# TSOC_ESP32S.net
KiCad netlist of a schematic drawn in EAGLE
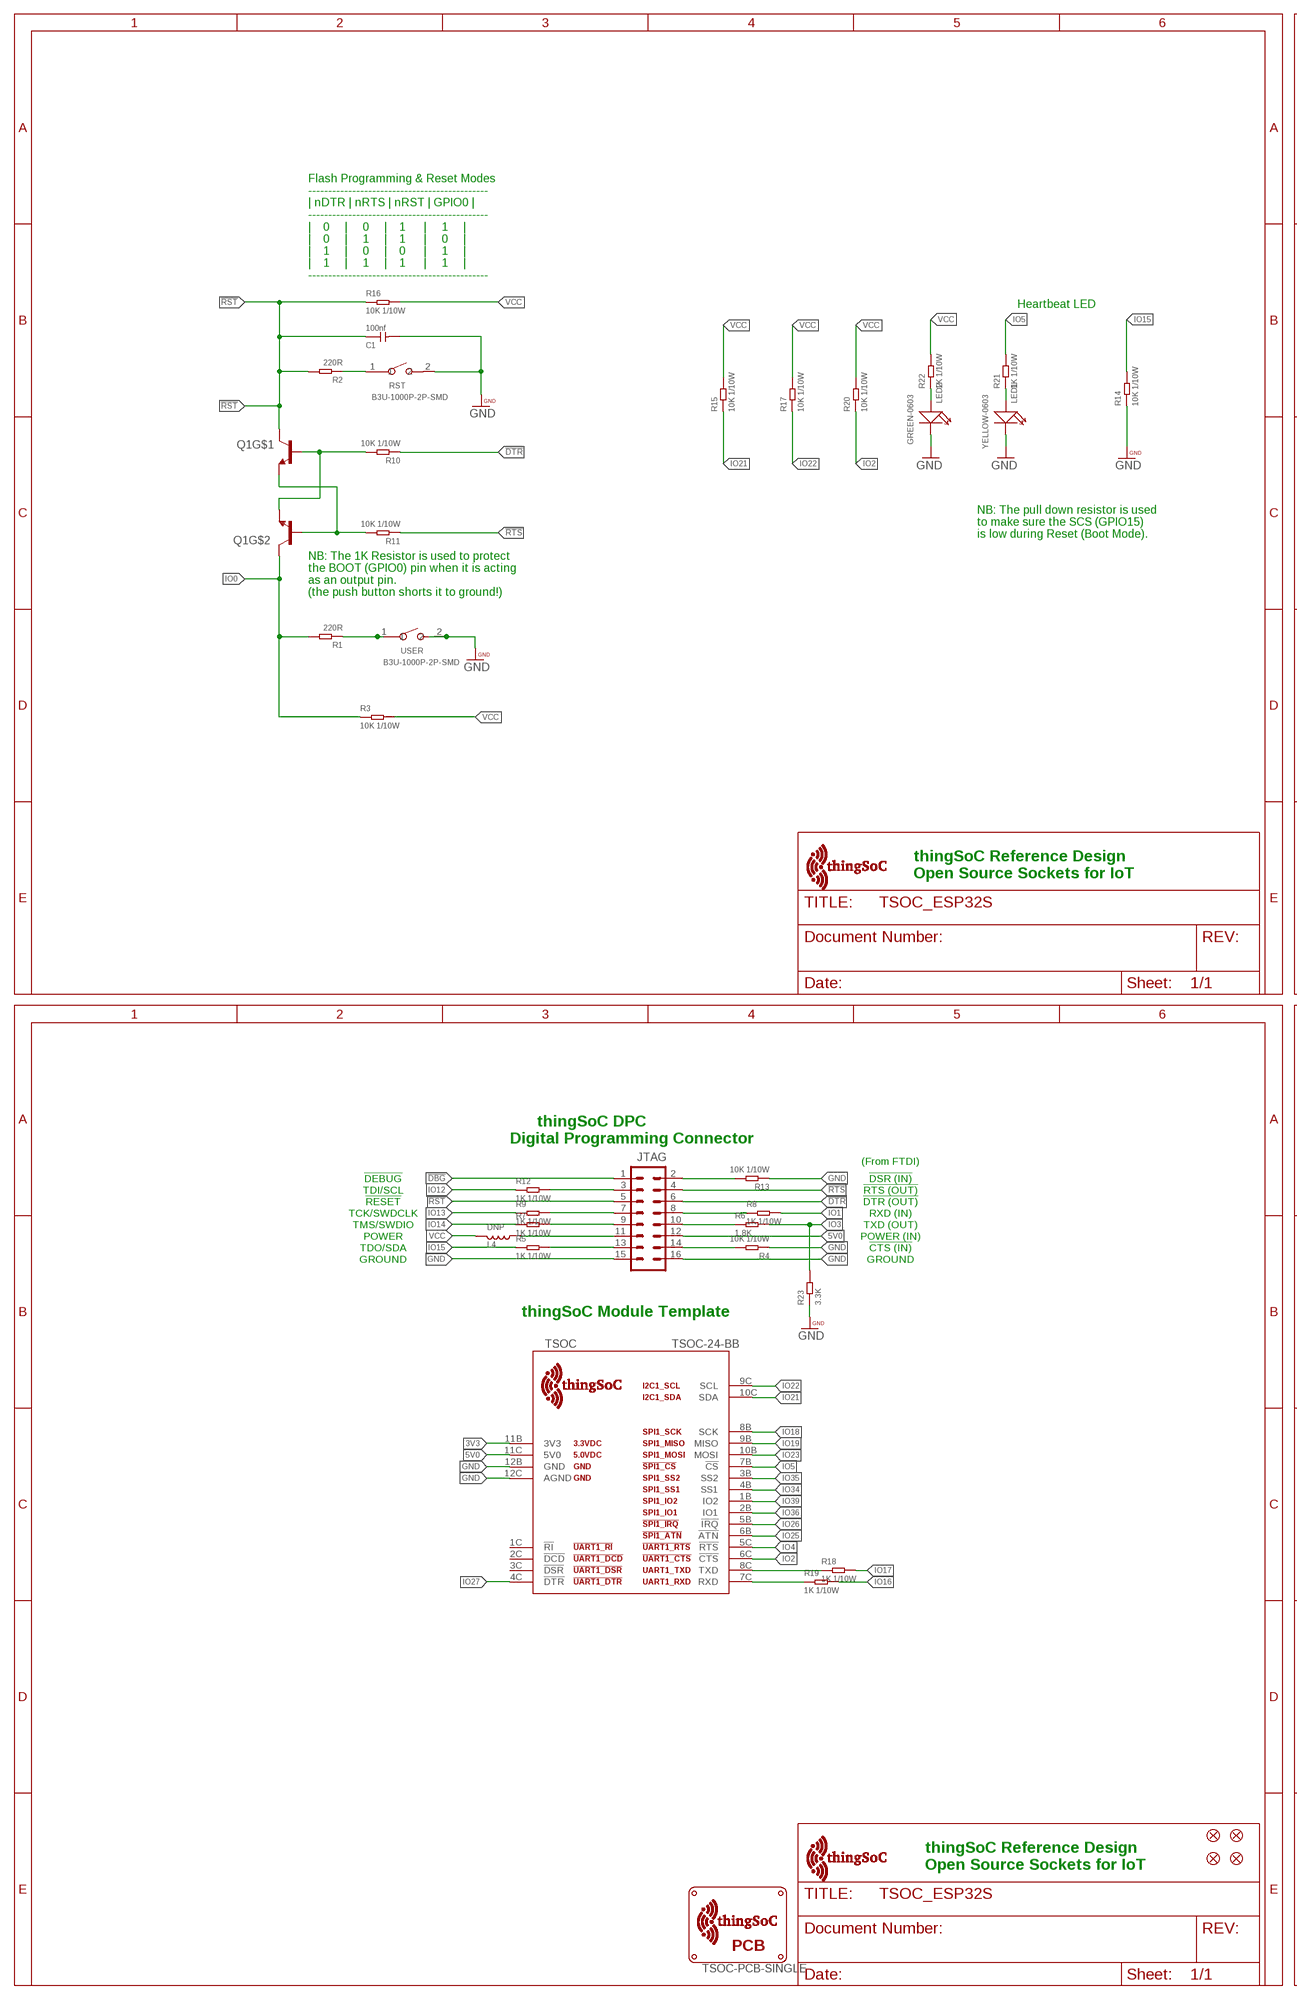
[diagram p0: schematic, sheet 1, part 1 of 2]
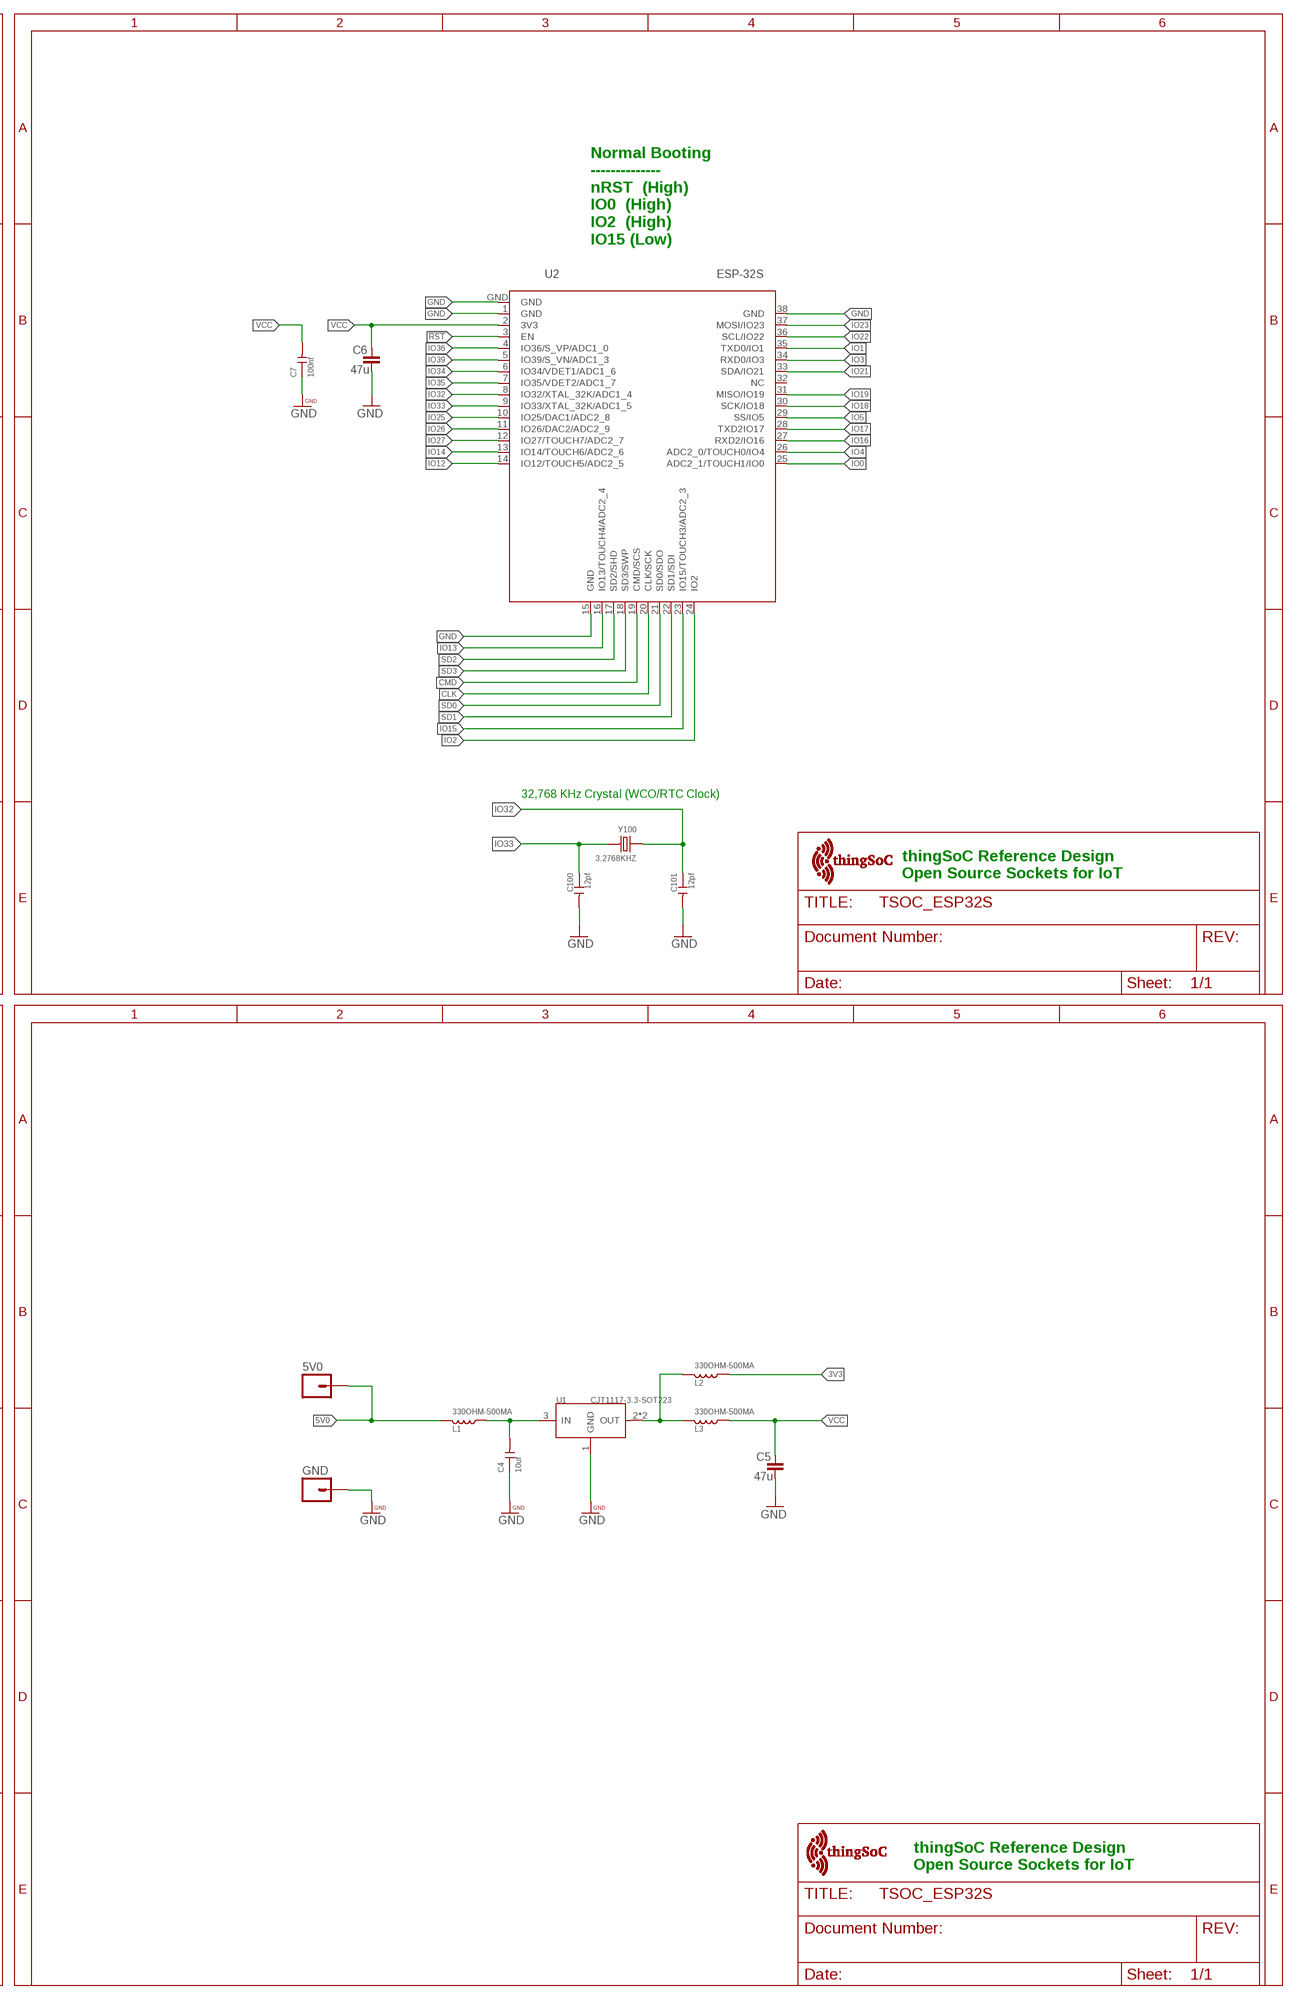
[diagram p1: schematic, sheet 1, part 2 of 2]

(export (version "E")
  (design (tool "Eeschema 10.0.6"))
  (components
    (comp (ref "$$U$1")
      (value "TSOC-LOGO-SMALL")
      (footprint "eagle-import:TSOC-LOGO-SML")
      (libsource (lib "eagle-import") (part "TSOC-LOGO-SMALL"))
    )
    (comp (ref "$$U$2")
      (value "TSOC-LOGO-SMALL")
      (footprint "eagle-import:TSOC-LOGO-SML")
      (libsource (lib "eagle-import") (part "TSOC-LOGO-SMALL"))
    )
    (comp (ref "5V0")
      (value "M01PTH")
      (footprint "eagle-import:1X01")
      (libsource (lib "eagle-import") (part "M01PTH"))
    )
    (comp (ref "BRD")
      (value "TSOC-PCB-SINGLE")
      (footprint "eagle-import:TSOC-BB-BRD-DIM")
      (libsource (lib "eagle-import") (part "TSOC-PCB-SINGLE"))
    )
    (comp (ref "C1")
      (value "100nf")
      (footprint "eagle-import:C0603")
      (fields (field (name "MPN") "CC0603KRX7R9BB104"))
      (libsource (lib "eagle-import") (part "CERAMIC-100NF-50V-10%-X7R(0603)"))
    )
    (comp (ref "C4")
      (value "10uf")
      (footprint "eagle-import:C0603")
      (fields (field (name "MPN") "CC0603KRX5R6BB106"))
      (libsource (lib "eagle-import") (part "CERAMIC-10UF-10V-10%-X5R(0603)"))
    )
    (comp (ref "C5")
      (value "47u")
      (footprint "eagle-import:C1206")
      (libsource (lib "eagle-import") (part "CAPACITOR-1206"))
    )
    (comp (ref "C6")
      (value "47u")
      (footprint "eagle-import:C1206")
      (libsource (lib "eagle-import") (part "CAPACITOR-1206"))
    )
    (comp (ref "C7")
      (value "100nf")
      (footprint "eagle-import:C0603")
      (fields (field (name "MPN") "CC0603KRX5R6BB106"))
      (libsource (lib "eagle-import") (part "CERAMIC-10UF-10V-10%-X5R(0603)"))
    )
    (comp (ref "C100")
      (value "12pf")
      (footprint "eagle-import:C0603")
      (fields (field (name "MPN") "CC0603JRNPO9BN120"))
      (libsource (lib "eagle-import") (part "CERAMIC-12PF-50V-5%-NPO(0603)"))
    )
    (comp (ref "C101")
      (value "12pf")
      (footprint "eagle-import:C0603")
      (fields (field (name "MPN") "CC0603JRNPO9BN120"))
      (libsource (lib "eagle-import") (part "CERAMIC-12PF-50V-5%-NPO(0603)"))
    )
    (comp (ref "FID1")
      (value "FIDUCIALUFIDUCIAL")
      (footprint "eagle-import:MICRO-FIDUCIAL")
      (libsource (lib "eagle-import") (part "FIDUCIALUFIDUCIAL"))
    )
    (comp (ref "FID2")
      (value "FIDUCIALUFIDUCIAL")
      (footprint "eagle-import:MICRO-FIDUCIAL")
      (libsource (lib "eagle-import") (part "FIDUCIALUFIDUCIAL"))
    )
    (comp (ref "FID3")
      (value "FIDUCIALUFIDUCIAL")
      (footprint "eagle-import:MICRO-FIDUCIAL")
      (libsource (lib "eagle-import") (part "FIDUCIALUFIDUCIAL"))
    )
    (comp (ref "FID4")
      (value "FIDUCIALUFIDUCIAL")
      (footprint "eagle-import:MICRO-FIDUCIAL")
      (libsource (lib "eagle-import") (part "FIDUCIALUFIDUCIAL"))
    )
    (comp (ref "GND")
      (value "M01PTH")
      (footprint "eagle-import:1X01")
      (libsource (lib "eagle-import") (part "M01PTH"))
    )
    (comp (ref "JTAG")
      (value "M08X2")
      (footprint "eagle-import:2X8")
      (libsource (lib "eagle-import") (part "M08X2"))
    )
    (comp (ref "L1")
      (value "330OHM-500MA")
      (footprint "eagle-import:L0603")
      (fields (field (name "MPN") "BLM18AG121SN1D"))
      (libsource (lib "eagle-import") (part "SMD-FERRITE-CHIP-120-OHM-500MA(0603)"))
    )
    (comp (ref "L2")
      (value "330OHM-500MA")
      (footprint "eagle-import:L0603")
      (fields (field (name "MPN") "BLM18AG121SN1D"))
      (libsource (lib "eagle-import") (part "SMD-FERRITE-CHIP-120-OHM-500MA(0603)"))
    )
    (comp (ref "L3")
      (value "330OHM-500MA")
      (footprint "eagle-import:L0603")
      (fields (field (name "MPN") "BLM18AG121SN1D"))
      (libsource (lib "eagle-import") (part "SMD-FERRITE-CHIP-120-OHM-500MA(0603)"))
    )
    (comp (ref "L4")
      (value "DNP")
      (footprint "eagle-import:L0603")
      (fields (field (name "MPN") "BLM18AG121SN1D"))
      (libsource (lib "eagle-import") (part "SMD-FERRITE-CHIP-120-OHM-500MA(0603)"))
    )
    (comp (ref "LED1")
      (value "YELLOW-0603")
      (footprint "eagle-import:LED-0603")
      (fields (field (name "MPN") "19-217-Y5C-AM1N1VY-3T"))
      (libsource (lib "eagle-import") (part "SMD-LED-CLEAR-YELLOW(0603)"))
    )
    (comp (ref "LED2")
      (value "GREEN-0603")
      (footprint "eagle-import:LED-0603")
      (fields (field (name "MPN") "19-217-G7C-AN1P2-3T"))
      (libsource (lib "eagle-import") (part "SMD-LED-CLEAR-GREEN(0603)"))
    )
    (comp (ref "Q1")
      (value "MMBT2222A")
      (footprint "eagle-import:SOT363")
      (libsource (lib "eagle-import") (part "MMDT3904"))
    )
    (comp (ref "R1")
      (value "220R")
      (footprint "eagle-import:R0603")
      (fields (field (name "MPN") "RC0603JR-07220RL"))
      (libsource (lib "eagle-import") (part "SMD-RES-220R-5%-1/10W(0603)"))
    )
    (comp (ref "R2")
      (value "220R")
      (footprint "eagle-import:R0603")
      (fields (field (name "MPN") "RC0603JR-07220RL"))
      (libsource (lib "eagle-import") (part "SMD-RES-220R-5%-1/10W(0603)"))
    )
    (comp (ref "R3")
      (value "10K 1/10W")
      (footprint "eagle-import:R0603")
      (fields (field (name "MPN") "RC0603JR-0710KL"))
      (libsource (lib "eagle-import") (part "SMD-RES-10K-5%-1/10W(0603)"))
    )
    (comp (ref "R4")
      (value "10K 1/10W")
      (footprint "eagle-import:R0603")
      (fields (field (name "MPN") "RC0603JR-0710KL"))
      (libsource (lib "eagle-import") (part "SMD-RES-10K-5%-1/10W(0603)"))
    )
    (comp (ref "R5")
      (value "1K 1/10W")
      (footprint "eagle-import:R0603")
      (fields (field (name "MPN") "RC0603JR-071KL"))
      (libsource (lib "eagle-import") (part "SMD-RES-1K-5%-1/10W(0603)"))
    )
    (comp (ref "R6")
      (value "1.8K")
      (footprint "eagle-import:R0603")
      (fields (field (name "MPN") "RC0603FR-071K8L"))
      (libsource (lib "eagle-import") (part "SMD-RES-1.8K-1%-1/10W(0603)"))
    )
    (comp (ref "R7")
      (value "1K 1/10W")
      (footprint "eagle-import:R0603")
      (fields (field (name "MPN") "RC0603JR-071KL"))
      (libsource (lib "eagle-import") (part "SMD-RES-1K-5%-1/10W(0603)"))
    )
    (comp (ref "R8")
      (value "1K 1/10W")
      (footprint "eagle-import:R0603")
      (fields (field (name "MPN") "RC0603JR-071KL"))
      (libsource (lib "eagle-import") (part "SMD-RES-1K-5%-1/10W(0603)"))
    )
    (comp (ref "R9")
      (value "1K 1/10W")
      (footprint "eagle-import:R0603")
      (fields (field (name "MPN") "RC0603JR-071KL"))
      (libsource (lib "eagle-import") (part "SMD-RES-1K-5%-1/10W(0603)"))
    )
    (comp (ref "R10")
      (value "10K 1/10W")
      (footprint "eagle-import:R0603")
      (fields (field (name "MPN") "RC0603JR-0710KL"))
      (libsource (lib "eagle-import") (part "SMD-RES-10K-5%-1/10W(0603)"))
    )
    (comp (ref "R11")
      (value "10K 1/10W")
      (footprint "eagle-import:R0603")
      (fields (field (name "MPN") "RC0603JR-0710KL"))
      (libsource (lib "eagle-import") (part "SMD-RES-10K-5%-1/10W(0603)"))
    )
    (comp (ref "R12")
      (value "1K 1/10W")
      (footprint "eagle-import:R0603")
      (fields (field (name "MPN") "RC0603JR-071KL"))
      (libsource (lib "eagle-import") (part "SMD-RES-1K-5%-1/10W(0603)"))
    )
    (comp (ref "R13")
      (value "10K 1/10W")
      (footprint "eagle-import:R0603")
      (fields (field (name "MPN") "RC0603JR-0710KL"))
      (libsource (lib "eagle-import") (part "SMD-RES-10K-5%-1/10W(0603)"))
    )
    (comp (ref "R14")
      (value "10K 1/10W")
      (footprint "eagle-import:R0603")
      (fields (field (name "MPN") "RC0603JR-0710KL"))
      (libsource (lib "eagle-import") (part "SMD-RES-10K-5%-1/10W(0603)"))
    )
    (comp (ref "R15")
      (value "10K 1/10W")
      (footprint "eagle-import:R0603")
      (fields (field (name "MPN") "RC0603JR-0710KL"))
      (libsource (lib "eagle-import") (part "SMD-RES-10K-5%-1/10W(0603)"))
    )
    (comp (ref "R16")
      (value "10K 1/10W")
      (footprint "eagle-import:R0603")
      (fields (field (name "MPN") "RC0603JR-0710KL"))
      (libsource (lib "eagle-import") (part "SMD-RES-10K-5%-1/10W(0603)"))
    )
    (comp (ref "R17")
      (value "10K 1/10W")
      (footprint "eagle-import:R0603")
      (fields (field (name "MPN") "RC0603JR-0710KL"))
      (libsource (lib "eagle-import") (part "SMD-RES-10K-5%-1/10W(0603)"))
    )
    (comp (ref "R18")
      (value "1K 1/10W")
      (footprint "eagle-import:R0603")
      (fields (field (name "MPN") "RC0603JR-071KL"))
      (libsource (lib "eagle-import") (part "SMD-RES-1K-5%-1/10W(0603)"))
    )
    (comp (ref "R19")
      (value "1K 1/10W")
      (footprint "eagle-import:R0603")
      (fields (field (name "MPN") "RC0603JR-071KL"))
      (libsource (lib "eagle-import") (part "SMD-RES-1K-5%-1/10W(0603)"))
    )
    (comp (ref "R20")
      (value "10K 1/10W")
      (footprint "eagle-import:R0603")
      (fields (field (name "MPN") "RC0603JR-0710KL"))
      (libsource (lib "eagle-import") (part "SMD-RES-10K-5%-1/10W(0603)"))
    )
    (comp (ref "R21")
      (value "1K 1/10W")
      (footprint "eagle-import:R0603")
      (fields (field (name "MPN") "RC0603JR-071KL"))
      (libsource (lib "eagle-import") (part "SMD-RES-1K-5%-1/10W(0603)"))
    )
    (comp (ref "R22")
      (value "1K 1/10W")
      (footprint "eagle-import:R0603")
      (fields (field (name "MPN") "RC0603JR-071KL"))
      (libsource (lib "eagle-import") (part "SMD-RES-1K-5%-1/10W(0603)"))
    )
    (comp (ref "R23")
      (value "3.3K")
      (footprint "eagle-import:R0603")
      (fields (field (name "MPN") "RC0603FR-073K3L"))
      (libsource (lib "eagle-import") (part "SMD-RES-3.3K-1%-1/10W(0603)"))
    )
    (comp (ref "RST")
      (value "B3U-1000P-2P-SMD")
      (footprint "eagle-import:SW2-2.6-3.0X2.5X1.2+0.4MM")
      (libsource (lib "eagle-import") (part "SMD-BUTTON(2P-3.0X2.5X1.2+0.4MM)-B3U-1000P-2P-SMD"))
    )
    (comp (ref "TSOC")
      (value "TSOC-24-BB")
      (footprint "eagle-import:TSOC-BB-S24")
      (libsource (lib "eagle-import") (part "TSOC-24-BB"))
    )
    (comp (ref "U$101")
      (value "TSOC-LOGO-SMALL")
      (footprint "eagle-import:TSOC-LOGO-SML")
      (libsource (lib "eagle-import") (part "TSOC-LOGO-SMALL"))
    )
    (comp (ref "U$102")
      (value "TSOC-LOGO-LRG")
      (footprint "eagle-import:TSOC-LOGO-LRG")
      (libsource (lib "eagle-import") (part "TSOC-LOGO-LRG"))
    )
    (comp (ref "U1")
      (value "CJT1117-3.3-SOT223")
      (footprint "eagle-import:SOT-223")
      (fields (field (name "MPN") "CJT1117-3.3"))
      (libsource (lib "eagle-import") (part "PMIC-CJT1117-3.3(SOT223)"))
    )
    (comp (ref "U2")
      (value "ESP-32S")
      (footprint "eagle-import:ESP-32S")
      (libsource (lib "eagle-import") (part "ESP-32S"))
    )
    (comp (ref "USER")
      (value "B3U-1000P-2P-SMD")
      (footprint "eagle-import:SW2-2.6-3.0X2.5X1.2+0.4MM")
      (libsource (lib "eagle-import") (part "SMD-BUTTON(2P-3.0X2.5X1.2+0.4MM)-B3U-1000P-2P-SMD"))
    )
    (comp (ref "Y100")
      (value "3.2768KHZ")
      (footprint "eagle-import:X2-SMD-L2.0X1.2X0.55MM")
      (fields (field (name "MPN") "FC-12M"))
      (libsource (lib "eagle-import") (part "SMD-CRYSTAL-32.768KHZ-12.5PF-20PPM-90K(2P-L2.0X1.2MM)"))
    )
  )
  (nets
    (net (code "1") (name "/~{DBG}") (class "Default")
      (node (ref "JTAG") (pin "1") (pinfunction "1_1") (pintype "passive"))
    )
    (net (code "2") (name "/~{DTR}") (class "Default")
      (node (ref "JTAG") (pin "6") (pinfunction "6_6") (pintype "passive"))
      (node (ref "R10") (pin "1") (pinfunction "1_1") (pintype "passive"))
    )
    (net (code "3") (name "/~{RST}") (class "Default")
      (node (ref "C1") (pin "1") (pinfunction "1_1") (pintype "passive"))
      (node (ref "JTAG") (pin "5") (pinfunction "5_5") (pintype "passive"))
      (node (ref "Q1") (pin "3") (pinfunction "C_3") (pintype "passive"))
      (node (ref "R16") (pin "1") (pinfunction "1_1") (pintype "passive"))
      (node (ref "R2") (pin "2") (pinfunction "2_2") (pintype "passive"))
      (node (ref "U2") (pin "3") (pinfunction "EN_3") (pintype "bidirectional"))
    )
    (net (code "4") (name "/~{RTS}") (class "Default")
      (node (ref "JTAG") (pin "4") (pinfunction "4_4") (pintype "passive"))
      (node (ref "R11") (pin "1") (pinfunction "1_1") (pintype "passive"))
    )
    (net (code "5") (name "3V3") (class "Default")
      (node (ref "L2") (pin "2") (pinfunction "2_2") (pintype "passive"))
      (node (ref "TSOC") (pin "11B") (pinfunction "3V3_11B") (pintype "bidirectional"))
    )
    (net (code "6") (name "5V0") (class "Default")
      (node (ref "5V0") (pin "1") (pinfunction "1_1") (pintype "passive"))
      (node (ref "JTAG") (pin "12") (pinfunction "12_12") (pintype "passive"))
      (node (ref "L1") (pin "1") (pinfunction "1_1") (pintype "passive"))
      (node (ref "TSOC") (pin "11C") (pinfunction "5V0_11C") (pintype "bidirectional"))
    )
    (net (code "7") (name "CLK") (class "Default")
      (node (ref "U2") (pin "20") (pinfunction "CLK/SCK_20") (pintype "bidirectional"))
    )
    (net (code "8") (name "CMD") (class "Default")
      (node (ref "U2") (pin "19") (pinfunction "CMD/SCS_19") (pintype "bidirectional"))
    )
    (net (code "9") (name "GND") (class "Default")
      (node (ref "C1") (pin "2") (pinfunction "2_2") (pintype "passive"))
      (node (ref "C100") (pin "2") (pinfunction "2_2") (pintype "passive"))
      (node (ref "C101") (pin "2") (pinfunction "2_2") (pintype "passive"))
      (node (ref "C4") (pin "1") (pinfunction "1_1") (pintype "passive"))
      (node (ref "C5") (pin "1") (pinfunction "1_1") (pintype "passive"))
      (node (ref "C6") (pin "1") (pinfunction "1_1") (pintype "passive"))
      (node (ref "C7") (pin "1") (pinfunction "1_1") (pintype "passive"))
      (node (ref "GND") (pin "1") (pinfunction "1_1") (pintype "passive"))
      (node (ref "JTAG") (pin "15") (pinfunction "15_15") (pintype "passive"))
      (node (ref "JTAG") (pin "16") (pinfunction "16_16") (pintype "passive"))
      (node (ref "LED1") (pin "-") (pinfunction "-_-") (pintype "passive"))
      (node (ref "LED2") (pin "-") (pinfunction "-_-") (pintype "passive"))
      (node (ref "R13") (pin "1") (pinfunction "1_1") (pintype "passive"))
      (node (ref "R14") (pin "1") (pinfunction "1_1") (pintype "passive"))
      (node (ref "R23") (pin "1") (pinfunction "1_1") (pintype "passive"))
      (node (ref "R4") (pin "1") (pinfunction "1_1") (pintype "passive"))
      (node (ref "RST") (pin "2") (pinfunction "2_2") (pintype "bidirectional"))
      (node (ref "TSOC") (pin "12B") (pinfunction "GND_12B") (pintype "bidirectional"))
      (node (ref "TSOC") (pin "12C") (pinfunction "AGND_12C") (pintype "bidirectional"))
      (node (ref "U1") (pin "1") (pinfunction "GND_1") (pintype "bidirectional"))
      (node (ref "U2") (pin "1") (pinfunction "GND_1") (pintype "bidirectional"))
      (node (ref "U2") (pin "15") (pinfunction "GND_15") (pintype "bidirectional"))
      (node (ref "U2") (pin "38") (pinfunction "GND_38") (pintype "bidirectional"))
      (node (ref "U2") (pin "GND") (pinfunction "GND_GND") (pintype "bidirectional"))
      (node (ref "USER") (pin "2") (pinfunction "2_2") (pintype "bidirectional"))
    )
    (net (code "10") (name "IO0") (class "Default")
      (node (ref "Q1") (pin "6") (pinfunction "C_6") (pintype "passive"))
      (node (ref "R1") (pin "2") (pinfunction "2_2") (pintype "passive"))
      (node (ref "R3") (pin "1") (pinfunction "1_1") (pintype "passive"))
      (node (ref "U2") (pin "25") (pinfunction "ADC2_1/TOUCH1/IO0_25") (pintype "bidirectional"))
    )
    (net (code "11") (name "IO1") (class "Default")
      (node (ref "R8") (pin "2") (pinfunction "2_2") (pintype "passive"))
      (node (ref "U2") (pin "35") (pinfunction "TXD0/IO1_35") (pintype "bidirectional"))
    )
    (net (code "12") (name "IO2") (class "Default")
      (node (ref "R20") (pin "1") (pinfunction "1_1") (pintype "passive"))
      (node (ref "TSOC") (pin "6C") (pinfunction "~{CTS}_6C") (pintype "bidirectional"))
      (node (ref "U2") (pin "24") (pinfunction "IO2_24") (pintype "bidirectional"))
    )
    (net (code "13") (name "IO3") (class "Default")
      (node (ref "R23") (pin "2") (pinfunction "2_2") (pintype "passive"))
      (node (ref "R6") (pin "2") (pinfunction "2_2") (pintype "passive"))
      (node (ref "U2") (pin "34") (pinfunction "RXD0/IO3_34") (pintype "bidirectional"))
    )
    (net (code "14") (name "IO4") (class "Default")
      (node (ref "TSOC") (pin "5C") (pinfunction "~{RTS}_5C") (pintype "bidirectional"))
      (node (ref "U2") (pin "26") (pinfunction "ADC2_0/TOUCH0/IO4_26") (pintype "bidirectional"))
    )
    (net (code "15") (name "IO5") (class "Default")
      (node (ref "R21") (pin "2") (pinfunction "2_2") (pintype "passive"))
      (node (ref "TSOC") (pin "7B") (pinfunction "~{CS}_7B") (pintype "bidirectional"))
      (node (ref "U2") (pin "29") (pinfunction "SS/IO5_29") (pintype "bidirectional"))
    )
    (net (code "16") (name "IO12") (class "Default")
      (node (ref "R12") (pin "1") (pinfunction "1_1") (pintype "passive"))
      (node (ref "U2") (pin "14") (pinfunction "IO12/TOUCH5/ADC2_5_14") (pintype "bidirectional"))
    )
    (net (code "17") (name "IO13") (class "Default")
      (node (ref "R9") (pin "1") (pinfunction "1_1") (pintype "passive"))
      (node (ref "U2") (pin "16") (pinfunction "IO13/TOUCH4/ADC2_4_16") (pintype "bidirectional"))
    )
    (net (code "18") (name "IO14") (class "Default")
      (node (ref "R7") (pin "1") (pinfunction "1_1") (pintype "passive"))
      (node (ref "U2") (pin "13") (pinfunction "IO14/TOUCH6/ADC2_6_13") (pintype "bidirectional"))
    )
    (net (code "19") (name "IO15") (class "Default")
      (node (ref "R14") (pin "2") (pinfunction "2_2") (pintype "passive"))
      (node (ref "R5") (pin "1") (pinfunction "1_1") (pintype "passive"))
      (node (ref "U2") (pin "23") (pinfunction "IO15/TOUCH3/ADC2_3_23") (pintype "bidirectional"))
    )
    (net (code "20") (name "IO16") (class "Default")
      (node (ref "R19") (pin "2") (pinfunction "2_2") (pintype "passive"))
      (node (ref "U2") (pin "27") (pinfunction "RXD2/IO16_27") (pintype "bidirectional"))
    )
    (net (code "21") (name "IO17") (class "Default")
      (node (ref "R18") (pin "2") (pinfunction "2_2") (pintype "passive"))
      (node (ref "U2") (pin "28") (pinfunction "TXD2IO17_28") (pintype "bidirectional"))
    )
    (net (code "22") (name "IO18") (class "Default")
      (node (ref "TSOC") (pin "8B") (pinfunction "SCK_8B") (pintype "bidirectional"))
      (node (ref "U2") (pin "30") (pinfunction "SCK/IO18_30") (pintype "bidirectional"))
    )
    (net (code "23") (name "IO19") (class "Default")
      (node (ref "TSOC") (pin "9B") (pinfunction "MISO_9B") (pintype "bidirectional"))
      (node (ref "U2") (pin "31") (pinfunction "MISO/IO19_31") (pintype "bidirectional"))
    )
    (net (code "24") (name "IO21") (class "Default")
      (node (ref "R15") (pin "1") (pinfunction "1_1") (pintype "passive"))
      (node (ref "TSOC") (pin "10C") (pinfunction "SDA_10C") (pintype "bidirectional"))
      (node (ref "U2") (pin "33") (pinfunction "SDA/IO21_33") (pintype "bidirectional"))
    )
    (net (code "25") (name "IO22") (class "Default")
      (node (ref "R17") (pin "1") (pinfunction "1_1") (pintype "passive"))
      (node (ref "TSOC") (pin "9C") (pinfunction "SCL_9C") (pintype "bidirectional"))
      (node (ref "U2") (pin "36") (pinfunction "SCL/IO22_36") (pintype "bidirectional"))
    )
    (net (code "26") (name "IO23") (class "Default")
      (node (ref "TSOC") (pin "10B") (pinfunction "MOSI_10B") (pintype "bidirectional"))
      (node (ref "U2") (pin "37") (pinfunction "MOSI/IO23_37") (pintype "bidirectional"))
    )
    (net (code "27") (name "IO25") (class "Default")
      (node (ref "TSOC") (pin "6B") (pinfunction "~{ATN}_6B") (pintype "bidirectional"))
      (node (ref "U2") (pin "10") (pinfunction "IO25/DAC1/ADC2_8_10") (pintype "bidirectional"))
    )
    (net (code "28") (name "IO26") (class "Default")
      (node (ref "TSOC") (pin "5B") (pinfunction "~{IRQ}_5B") (pintype "bidirectional"))
      (node (ref "U2") (pin "11") (pinfunction "IO26/DAC2/ADC2_9_11") (pintype "bidirectional"))
    )
    (net (code "29") (name "IO27") (class "Default")
      (node (ref "TSOC") (pin "4C") (pinfunction "~{DTR}_4C") (pintype "bidirectional"))
      (node (ref "U2") (pin "12") (pinfunction "IO27/TOUCH7/ADC2_7_12") (pintype "bidirectional"))
    )
    (net (code "30") (name "IO32") (class "Default")
      (node (ref "C101") (pin "1") (pinfunction "1_1") (pintype "passive"))
      (node (ref "U2") (pin "8") (pinfunction "IO32/XTAL_32K/ADC1_4_8") (pintype "bidirectional"))
      (node (ref "Y100") (pin "1") (pinfunction "1_1") (pintype "passive"))
    )
    (net (code "31") (name "IO33") (class "Default")
      (node (ref "C100") (pin "1") (pinfunction "1_1") (pintype "passive"))
      (node (ref "U2") (pin "9") (pinfunction "IO33/XTAL_32K/ADC1_5_9") (pintype "bidirectional"))
      (node (ref "Y100") (pin "2") (pinfunction "2_2") (pintype "passive"))
    )
    (net (code "32") (name "IO34") (class "Default")
      (node (ref "TSOC") (pin "4B") (pinfunction "SS1_4B") (pintype "bidirectional"))
      (node (ref "U2") (pin "6") (pinfunction "IO34/VDET1/ADC1_6_6") (pintype "bidirectional"))
    )
    (net (code "33") (name "IO35") (class "Default")
      (node (ref "TSOC") (pin "3B") (pinfunction "SS2_3B") (pintype "bidirectional"))
      (node (ref "U2") (pin "7") (pinfunction "IO35/VDET2/ADC1_7_7") (pintype "bidirectional"))
    )
    (net (code "34") (name "IO36") (class "Default")
      (node (ref "TSOC") (pin "2B") (pinfunction "IO1_2B") (pintype "bidirectional"))
      (node (ref "U2") (pin "4") (pinfunction "IO36/S_VP/ADC1_0_4") (pintype "bidirectional"))
    )
    (net (code "35") (name "IO39") (class "Default")
      (node (ref "TSOC") (pin "1B") (pinfunction "IO2_1B") (pintype "bidirectional"))
      (node (ref "U2") (pin "5") (pinfunction "IO39/S_VN/ADC1_3_5") (pintype "bidirectional"))
    )
    (net (code "36") (name "Net-(JTAG-Pad2)") (class "Default")
      (node (ref "JTAG") (pin "2") (pinfunction "2_2") (pintype "passive"))
      (node (ref "R13") (pin "2") (pinfunction "2_2") (pintype "passive"))
    )
    (net (code "37") (name "Net-(JTAG-Pad3)") (class "Default")
      (node (ref "JTAG") (pin "3") (pinfunction "3_3") (pintype "passive"))
      (node (ref "R12") (pin "2") (pinfunction "2_2") (pintype "passive"))
    )
    (net (code "38") (name "Net-(JTAG-Pad7)") (class "Default")
      (node (ref "JTAG") (pin "7") (pinfunction "7_7") (pintype "passive"))
      (node (ref "R9") (pin "2") (pinfunction "2_2") (pintype "passive"))
    )
    (net (code "39") (name "Net-(JTAG-Pad8)") (class "Default")
      (node (ref "JTAG") (pin "8") (pinfunction "8_8") (pintype "passive"))
      (node (ref "R8") (pin "1") (pinfunction "1_1") (pintype "passive"))
    )
    (net (code "40") (name "Net-(JTAG-Pad9)") (class "Default")
      (node (ref "JTAG") (pin "9") (pinfunction "9_9") (pintype "passive"))
      (node (ref "R7") (pin "2") (pinfunction "2_2") (pintype "passive"))
    )
    (net (code "41") (name "Net-(JTAG-Pad10)") (class "Default")
      (node (ref "JTAG") (pin "10") (pinfunction "10_10") (pintype "passive"))
      (node (ref "R6") (pin "1") (pinfunction "1_1") (pintype "passive"))
    )
    (net (code "42") (name "Net-(JTAG-Pad11)") (class "Default")
      (node (ref "JTAG") (pin "11") (pinfunction "11_11") (pintype "passive"))
      (node (ref "L4") (pin "2") (pinfunction "2_2") (pintype "passive"))
    )
    (net (code "43") (name "Net-(JTAG-Pad13)") (class "Default")
      (node (ref "JTAG") (pin "13") (pinfunction "13_13") (pintype "passive"))
      (node (ref "R5") (pin "2") (pinfunction "2_2") (pintype "passive"))
    )
    (net (code "44") (name "Net-(JTAG-Pad14)") (class "Default")
      (node (ref "JTAG") (pin "14") (pinfunction "14_14") (pintype "passive"))
      (node (ref "R4") (pin "2") (pinfunction "2_2") (pintype "passive"))
    )
    (net (code "45") (name "Net-(L2-Pad1)") (class "Default")
      (node (ref "L2") (pin "1") (pinfunction "1_1") (pintype "passive"))
      (node (ref "L3") (pin "1") (pinfunction "1_1") (pintype "passive"))
      (node (ref "U1") (pin "2") (pinfunction "OUT_2") (pintype "bidirectional"))
      (node (ref "U1") (pin "TER") (pinfunction "OUT_TER") (pintype "bidirectional"))
    )
    (net (code "46") (name "Net-(LED1-Pad+)") (class "Default")
      (node (ref "LED1") (pin "+") (pinfunction "+_+") (pintype "passive"))
      (node (ref "R21") (pin "1") (pinfunction "1_1") (pintype "passive"))
    )
    (net (code "47") (name "Net-(LED2-Pad+)") (class "Default")
      (node (ref "LED2") (pin "+") (pinfunction "+_+") (pintype "passive"))
      (node (ref "R22") (pin "1") (pinfunction "1_1") (pintype "passive"))
    )
    (net (code "48") (name "Net-(Q1A-B)") (class "Default")
      (node (ref "Q1") (pin "1") (pinfunction "E_1") (pintype "passive"))
      (node (ref "Q1") (pin "5") (pinfunction "B_5") (pintype "passive"))
      (node (ref "R10") (pin "2") (pinfunction "2_2") (pintype "passive"))
    )
    (net (code "49") (name "Net-(Q1A-E)") (class "Default")
      (node (ref "Q1") (pin "2") (pinfunction "B_2") (pintype "passive"))
      (node (ref "Q1") (pin "4") (pinfunction "E_4") (pintype "passive"))
      (node (ref "R11") (pin "2") (pinfunction "2_2") (pintype "passive"))
    )
    (net (code "50") (name "Net-(R1-Pad1)") (class "Default")
      (node (ref "R1") (pin "1") (pinfunction "1_1") (pintype "passive"))
      (node (ref "USER") (pin "1") (pinfunction "1_1") (pintype "bidirectional"))
    )
    (net (code "51") (name "Net-(R2-Pad1)") (class "Default")
      (node (ref "R2") (pin "1") (pinfunction "1_1") (pintype "passive"))
      (node (ref "RST") (pin "1") (pinfunction "1_1") (pintype "bidirectional"))
    )
    (net (code "52") (name "Net-(TSOC-RXD)") (class "Default")
      (node (ref "R19") (pin "1") (pinfunction "1_1") (pintype "passive"))
      (node (ref "TSOC") (pin "7C") (pinfunction "RXD_7C") (pintype "bidirectional"))
    )
    (net (code "53") (name "Net-(TSOC-TXD)") (class "Default")
      (node (ref "R18") (pin "1") (pinfunction "1_1") (pintype "passive"))
      (node (ref "TSOC") (pin "8C") (pinfunction "TXD_8C") (pintype "bidirectional"))
    )
    (net (code "54") (name "Net-(U1-IN)") (class "Default")
      (node (ref "C4") (pin "2") (pinfunction "2_2") (pintype "passive"))
      (node (ref "L1") (pin "2") (pinfunction "2_2") (pintype "passive"))
      (node (ref "U1") (pin "3") (pinfunction "IN_3") (pintype "bidirectional"))
    )
    (net (code "55") (name "SD0") (class "Default")
      (node (ref "U2") (pin "21") (pinfunction "SD0/SDO_21") (pintype "bidirectional"))
    )
    (net (code "56") (name "SD1") (class "Default")
      (node (ref "U2") (pin "22") (pinfunction "SD1/SDI_22") (pintype "bidirectional"))
    )
    (net (code "57") (name "SD2") (class "Default")
      (node (ref "U2") (pin "17") (pinfunction "SD2/SHD_17") (pintype "bidirectional"))
    )
    (net (code "58") (name "SD3") (class "Default")
      (node (ref "U2") (pin "18") (pinfunction "SD3/SWP_18") (pintype "bidirectional"))
    )
    (net (code "59") (name "VCC") (class "Default")
      (node (ref "C5") (pin "2") (pinfunction "2_2") (pintype "passive"))
      (node (ref "C6") (pin "2") (pinfunction "2_2") (pintype "passive"))
      (node (ref "C7") (pin "2") (pinfunction "2_2") (pintype "passive"))
      (node (ref "L3") (pin "2") (pinfunction "2_2") (pintype "passive"))
      (node (ref "L4") (pin "1") (pinfunction "1_1") (pintype "passive"))
      (node (ref "R15") (pin "2") (pinfunction "2_2") (pintype "passive"))
      (node (ref "R16") (pin "2") (pinfunction "2_2") (pintype "passive"))
      (node (ref "R17") (pin "2") (pinfunction "2_2") (pintype "passive"))
      (node (ref "R20") (pin "2") (pinfunction "2_2") (pintype "passive"))
      (node (ref "R22") (pin "2") (pinfunction "2_2") (pintype "passive"))
      (node (ref "R3") (pin "2") (pinfunction "2_2") (pintype "passive"))
      (node (ref "U2") (pin "2") (pinfunction "3V3_2") (pintype "bidirectional"))
    )
    (net (code "60") (name "unconnected-(TSOC-~{DCD}-Pad2C)") (class "Default")
      (node (ref "TSOC") (pin "2C") (pinfunction "~{DCD}_2C") (pintype "bidirectional"))
    )
    (net (code "61") (name "unconnected-(TSOC-~{DSR}-Pad3C)") (class "Default")
      (node (ref "TSOC") (pin "3C") (pinfunction "~{DSR}_3C") (pintype "bidirectional"))
    )
    (net (code "62") (name "unconnected-(TSOC-~{RI}-Pad1C)") (class "Default")
      (node (ref "TSOC") (pin "1C") (pinfunction "~{RI}_1C") (pintype "bidirectional"))
    )
    (net (code "63") (name "unconnected-(U2-NC-Pad32)") (class "Default")
      (node (ref "U2") (pin "32") (pinfunction "NC_32") (pintype "bidirectional"))
    )
  )
)
